# ChargeControl2019.net
KiCad netlist of a schematic drawn in Altium Designer
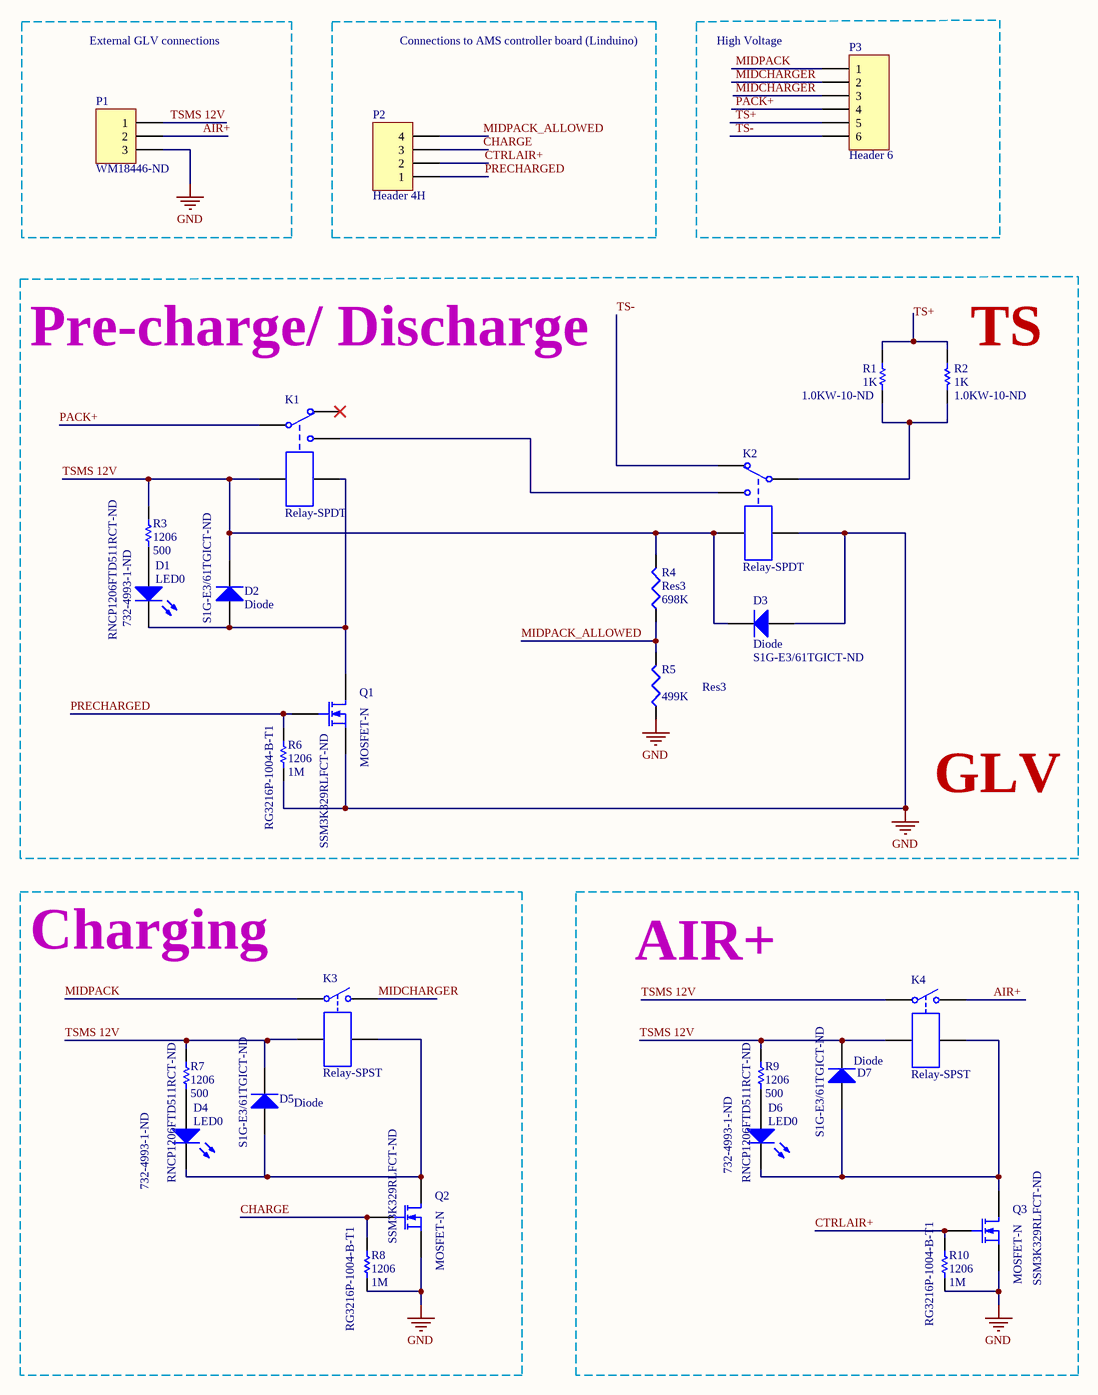
[diagram p0: ChargeControl2019.SchDoc]

(export (version "E")
  (design (tool "Eeschema 10.0.6"))
  (components
    (comp (ref "D1")
      (value "LED0")
      (footprint "LEDC3216X120NGRN")
      (description "Typical INFRARED GaAs LED")
      (fields
        (field (name "SUPPLIER PART NUMBER") "732-4993-1-ND")
        (field (name "PUBLISHER") "Altium Limited")
      )
      (libsource (lib "Miscellaneous Devices") (part "LED0"))
    )
    (comp (ref "D2")
      (value "Diode")
      (footprint "VISH-DO-214AC-SMA-2_N")
      (description "Switching diode")
      (fields
        (field (name "SUPPLIER PART NUMBER") "S1G-E3/61TGICT-ND")
        (field (name "PUBLISHER") "Altium Limited")
      )
      (libsource (lib "Miscellaneous Devices") (part "Diode"))
    )
    (comp (ref "D3")
      (value "Diode")
      (footprint "VISH-DO-214AC-SMA-2_N")
      (description "Switching diode")
      (fields
        (field (name "SUPPLIER PART NUMBER") "S1G-E3/61TGICT-ND")
        (field (name "PUBLISHER") "Altium Limited")
      )
      (libsource (lib "Miscellaneous Devices") (part "Diode"))
    )
    (comp (ref "D4")
      (value "LED0")
      (footprint "LEDC3216X120NGRN")
      (description "Typical INFRARED GaAs LED")
      (fields
        (field (name "SUPPLIER PART NUMBER") "732-4993-1-ND")
        (field (name "PUBLISHER") "Altium Limited")
      )
      (libsource (lib "Miscellaneous Devices") (part "LED0"))
    )
    (comp (ref "D5")
      (value "Diode")
      (footprint "VISH-DO-214AC-SMA-2_N")
      (description "Switching diode")
      (fields
        (field (name "SUPPLIER PART NUMBER") "S1G-E3/61TGICT-ND")
        (field (name "PUBLISHER") "Altium Limited")
      )
      (libsource (lib "Miscellaneous Devices") (part "Diode"))
    )
    (comp (ref "D6")
      (value "LED0")
      (footprint "LEDC3216X120NGRN")
      (description "Typical INFRARED GaAs LED")
      (fields
        (field (name "SUPPLIER PART NUMBER") "732-4993-1-ND")
        (field (name "PUBLISHER") "Altium Limited")
      )
      (libsource (lib "Miscellaneous Devices") (part "LED0"))
    )
    (comp (ref "D7")
      (value "Diode")
      (footprint "VISH-DO-214AC-SMA-2_N")
      (description "Switching diode")
      (fields
        (field (name "SUPPLIER PART NUMBER") "S1G-E3/61TGICT-ND")
        (field (name "PUBLISHER") "Altium Limited")
      )
      (libsource (lib "Miscellaneous Devices") (part "Diode"))
    )
    (comp (ref "K1")
      (value "Relay-SPDT")
      (footprint "G2RL1:G2RL14")
      (description "Single-Pole Dual-Throw Relay")
      (fields (field (name "PUBLISHER") "Altium Limited"))
      (libsource (lib "Miscellaneous Devices") (part "Relay-SPDT"))
    )
    (comp (ref "K2")
      (value "Relay-SPDT")
      (footprint "G2RL14")
      (description "Single-Pole Dual-Throw Relay")
      (fields (field (name "PUBLISHER") "Altium Limited"))
      (libsource (lib "Miscellaneous Devices") (part "Relay-SPDT"))
    )
    (comp (ref "K3")
      (value "Relay-SPST")
      (footprint "G2RL1ADC12")
      (description "Single-Pole Single-Throw Relay")
      (fields (field (name "PUBLISHER") "Altium Limited"))
      (libsource (lib "Miscellaneous Devices") (part "Relay-SPST"))
    )
    (comp (ref "K4")
      (value "Relay-SPST")
      (footprint "G2RL1ADC12")
      (description "Single-Pole Single-Throw Relay")
      (fields (field (name "PUBLISHER") "Altium Limited"))
      (libsource (lib "Miscellaneous Devices") (part "Relay-SPST"))
    )
    (comp (ref "P1")
      (value "Header 3")
      (footprint "Conn3pin")
      (description "3 pos wire to board")
      (fields (field (name "SUPPLIER PART NUMBER") "WM18446-ND") (field (name "PUBLISHER") "Altium Limited"))
      (libsource (lib "Miscellaneous Connectors") (part "Header 3"))
    )
    (comp (ref "P2")
      (value "Header 4H")
      (footprint "Conn4pin")
      (description "Header, 4-Pin, Right Angle")
      (fields (field (name "PUBLISHER") "Altium Limited"))
      (libsource (lib "Miscellaneous Connectors") (part "Header 4H"))
    )
    (comp (ref "P3")
      (value "Header 6")
      (footprint "Conn6pin")
      (description "Header, 6-Pin")
      (fields (field (name "PUBLISHER") "Altium Limited"))
      (libsource (lib "Miscellaneous Connectors") (part "Header 6"))
    )
    (comp (ref "Q1")
      (value "MOSFET-N")
      (footprint "SOT23-3")
      (description "N-Channel MOSFET")
      (fields
        (field (name "SUPPLIER PART NUMBER") "SSM3K329RLFCT-ND")
        (field (name "PUBLISHER") "Altium Limited")
      )
      (libsource (lib "Miscellaneous Devices") (part "MOSFET-N"))
    )
    (comp (ref "Q2")
      (value "MOSFET-N")
      (footprint "SOT23-3")
      (description "N-Channel MOSFET")
      (fields
        (field (name "SUPPLIER PART NUMBER") "SSM3K329RLFCT-ND")
        (field (name "PUBLISHER") "Altium Limited")
      )
      (libsource (lib "Miscellaneous Devices") (part "MOSFET-N"))
    )
    (comp (ref "Q3")
      (value "MOSFET-N")
      (footprint "SOT23-3")
      (description "N-Channel MOSFET")
      (fields
        (field (name "SUPPLIER PART NUMBER") "SSM3K329RLFCT-ND")
        (field (name "PUBLISHER") "Altium Limited")
      )
      (libsource (lib "Miscellaneous Devices") (part "MOSFET-N"))
    )
    (comp (ref "R1")
      (value "1K")
      (footprint "YAG_SQP10")
      (description "Resistor")
      (fields
        (field (name "SUPPLIER PART NUMBER") "1.0KW-10-ND")
        (field (name "Comment") "Res1")
        (field (name "PUBLISHER") "Altium Limited")
      )
      (libsource (lib "Miscellaneous Devices") (part "Res1"))
    )
    (comp (ref "R2")
      (value "1K")
      (footprint "YAG_SQP10")
      (description "Resistor")
      (fields
        (field (name "SUPPLIER PART NUMBER") "1.0KW-10-ND")
        (field (name "Comment") "Res1")
        (field (name "PUBLISHER") "Altium Limited")
      )
      (libsource (lib "Miscellaneous Devices") (part "Res1"))
    )
    (comp (ref "R3")
      (value "1206")
      (footprint "RESC3216X60N")
      (description "Resistor")
      (fields
        (field (name "ALTIUM_VALUE") "500")
        (field (name "SUPPLIER PART NUMBER") "RNCP1206FTD511RCT-ND")
        (field (name "PUBLISHER") "Altium Limited")
      )
      (libsource (lib "Miscellaneous Devices") (part "Res1"))
    )
    (comp (ref "R4")
      (value "Res3")
      (footprint "RESC3216X60N")
      (description "Resistor")
      (fields (field (name "ALTIUM_VALUE") "698K") (field (name "PUBLISHER") "Altium Limited"))
      (libsource (lib "Miscellaneous Devices") (part "Res3"))
    )
    (comp (ref "R5")
      (value "Res3")
      (footprint "RESC3216X60N")
      (description "Resistor")
      (fields (field (name "ALTIUM_VALUE") "499K") (field (name "PUBLISHER") "Altium Limited"))
      (libsource (lib "Miscellaneous Devices") (part "Res3"))
    )
    (comp (ref "R6")
      (value "1206")
      (footprint "RESC3216X60N")
      (description "Resistor")
      (fields
        (field (name "ALTIUM_VALUE") "1M")
        (field (name "SUPPLIER PART NUMBER") "RG3216P-1004-B-T1")
        (field (name "PUBLISHER") "Altium Limited")
      )
      (libsource (lib "Miscellaneous Devices") (part "Res1"))
    )
    (comp (ref "R7")
      (value "1206")
      (footprint "RESC3216X60N")
      (description "Resistor")
      (fields
        (field (name "ALTIUM_VALUE") "500")
        (field (name "SUPPLIER PART NUMBER") "RNCP1206FTD511RCT-ND")
        (field (name "PUBLISHER") "Altium Limited")
      )
      (libsource (lib "Miscellaneous Devices") (part "Res1"))
    )
    (comp (ref "R8")
      (value "1206")
      (footprint "RESC3216X60N")
      (description "Resistor")
      (fields
        (field (name "ALTIUM_VALUE") "1M")
        (field (name "SUPPLIER PART NUMBER") "RG3216P-1004-B-T1")
        (field (name "PUBLISHER") "Altium Limited")
      )
      (libsource (lib "Miscellaneous Devices") (part "Res1"))
    )
    (comp (ref "R9")
      (value "1206")
      (footprint "RESC3216X60N")
      (description "Resistor")
      (fields
        (field (name "ALTIUM_VALUE") "500")
        (field (name "SUPPLIER PART NUMBER") "RNCP1206FTD511RCT-ND")
        (field (name "PUBLISHER") "Altium Limited")
      )
      (libsource (lib "Miscellaneous Devices") (part "Res1"))
    )
    (comp (ref "R10")
      (value "1206")
      (footprint "RESC3216X60N")
      (description "Resistor")
      (fields
        (field (name "ALTIUM_VALUE") "1M")
        (field (name "SUPPLIER PART NUMBER") "RG3216P-1004-B-T1")
        (field (name "PUBLISHER") "Altium Limited")
      )
      (libsource (lib "Miscellaneous Devices") (part "Res1"))
    )
  )
  (nets
    (net (code "1") (name "/AIR+") (class "Default")
      (node (ref "K4") (pin "3") (pinfunction "3_3") (pintype "passive"))
      (node (ref "P1") (pin "2") (pinfunction "2_2") (pintype "passive"))
    )
    (net (code "2") (name "/CHARGE") (class "Default")
      (node (ref "P2") (pin "3") (pinfunction "3_3") (pintype "passive"))
      (node (ref "Q2") (pin "2") (pinfunction "G_2") (pintype "passive"))
      (node (ref "R8") (pin "2") (pinfunction "2_2") (pintype "passive"))
    )
    (net (code "3") (name "/CTRLAIR+") (class "Default")
      (node (ref "P2") (pin "2") (pinfunction "2_2") (pintype "passive"))
      (node (ref "Q3") (pin "2") (pinfunction "G_2") (pintype "passive"))
      (node (ref "R10") (pin "2") (pinfunction "2_2") (pintype "passive"))
    )
    (net (code "4") (name "/MIDCHARGER") (class "Default")
      (node (ref "K3") (pin "3") (pinfunction "3_3") (pintype "passive"))
      (node (ref "P3") (pin "2") (pinfunction "2_2") (pintype "passive"))
      (node (ref "P3") (pin "3") (pinfunction "3_3") (pintype "passive"))
    )
    (net (code "5") (name "/MIDPACK") (class "Default")
      (node (ref "K3") (pin "4") (pinfunction "4_4") (pintype "passive"))
      (node (ref "P3") (pin "1") (pinfunction "1_1") (pintype "passive"))
    )
    (net (code "6") (name "/MIDPACK_ALLOWED") (class "Default")
      (node (ref "P2") (pin "4") (pinfunction "4_4") (pintype "passive"))
      (node (ref "R4") (pin "1") (pinfunction "1_1") (pintype "passive"))
      (node (ref "R5") (pin "2") (pinfunction "2_2") (pintype "passive"))
    )
    (net (code "7") (name "/PACK+") (class "Default")
      (node (ref "K1") (pin "4") (pinfunction "4_4") (pintype "passive"))
      (node (ref "P3") (pin "4") (pinfunction "4_4") (pintype "passive"))
    )
    (net (code "8") (name "/PRECHARGED") (class "Default")
      (node (ref "P2") (pin "1") (pinfunction "1_1") (pintype "passive"))
      (node (ref "Q1") (pin "2") (pinfunction "G_2") (pintype "passive"))
      (node (ref "R6") (pin "2") (pinfunction "2_2") (pintype "passive"))
    )
    (net (code "9") (name "/TS+") (class "Default")
      (node (ref "P3") (pin "5") (pinfunction "5_5") (pintype "passive"))
      (node (ref "R1") (pin "2") (pinfunction "2_2") (pintype "passive"))
      (node (ref "R2") (pin "2") (pinfunction "2_2") (pintype "passive"))
    )
    (net (code "10") (name "/TS-") (class "Default")
      (node (ref "K2") (pin "2") (pinfunction "2_2") (pintype "passive"))
      (node (ref "P3") (pin "6") (pinfunction "6_6") (pintype "passive"))
    )
    (net (code "11") (name "/TSMS 12V") (class "Default")
      (node (ref "D2") (pin "2") (pinfunction "K_2") (pintype "passive"))
      (node (ref "D3") (pin "2") (pinfunction "K_2") (pintype "passive"))
      (node (ref "D5") (pin "2") (pinfunction "K_2") (pintype "passive"))
      (node (ref "D7") (pin "2") (pinfunction "K_2") (pintype "passive"))
      (node (ref "K1") (pin "1") (pinfunction "1_1") (pintype "passive"))
      (node (ref "K2") (pin "5") (pinfunction "5_5") (pintype "passive"))
      (node (ref "K3") (pin "1") (pinfunction "1_1") (pintype "passive"))
      (node (ref "K4") (pin "1") (pinfunction "1_1") (pintype "passive"))
      (node (ref "K4") (pin "4") (pinfunction "4_4") (pintype "passive"))
      (node (ref "P1") (pin "1") (pinfunction "1_1") (pintype "passive"))
      (node (ref "R3") (pin "1") (pinfunction "1_1") (pintype "passive"))
      (node (ref "R4") (pin "2") (pinfunction "2_2") (pintype "passive"))
      (node (ref "R7") (pin "1") (pinfunction "1_1") (pintype "passive"))
      (node (ref "R9") (pin "1") (pinfunction "1_1") (pintype "passive"))
    )
    (net (code "12") (name "GND") (class "Default")
      (node (ref "D3") (pin "1") (pinfunction "A_1") (pintype "passive"))
      (node (ref "K2") (pin "1") (pinfunction "1_1") (pintype "passive"))
      (node (ref "P1") (pin "3") (pinfunction "3_3") (pintype "passive"))
      (node (ref "Q1") (pin "3") (pinfunction "S_3") (pintype "passive"))
      (node (ref "Q2") (pin "3") (pinfunction "S_3") (pintype "passive"))
      (node (ref "Q3") (pin "3") (pinfunction "S_3") (pintype "passive"))
      (node (ref "R10") (pin "1") (pinfunction "1_1") (pintype "passive"))
      (node (ref "R5") (pin "1") (pinfunction "1_1") (pintype "passive"))
      (node (ref "R6") (pin "1") (pinfunction "1_1") (pintype "passive"))
      (node (ref "R8") (pin "1") (pinfunction "1_1") (pintype "passive"))
    )
    (net (code "13") (name "Net-(D1-A)") (class "Default")
      (node (ref "D1") (pin "1") (pinfunction "A_1") (pintype "passive"))
      (node (ref "R3") (pin "2") (pinfunction "2_2") (pintype "passive"))
    )
    (net (code "14") (name "Net-(D1-K)") (class "Default")
      (node (ref "D1") (pin "2") (pinfunction "K_2") (pintype "passive"))
      (node (ref "D2") (pin "1") (pinfunction "A_1") (pintype "passive"))
      (node (ref "K1") (pin "5") (pinfunction "5_5") (pintype "passive"))
      (node (ref "Q1") (pin "1") (pinfunction "D_1") (pintype "passive"))
    )
    (net (code "15") (name "Net-(D4-A)") (class "Default")
      (node (ref "D4") (pin "1") (pinfunction "A_1") (pintype "passive"))
      (node (ref "R7") (pin "2") (pinfunction "2_2") (pintype "passive"))
    )
    (net (code "16") (name "Net-(D4-K)") (class "Default")
      (node (ref "D4") (pin "2") (pinfunction "K_2") (pintype "passive"))
      (node (ref "D5") (pin "1") (pinfunction "A_1") (pintype "passive"))
      (node (ref "K3") (pin "5") (pinfunction "5_5") (pintype "passive"))
      (node (ref "Q2") (pin "1") (pinfunction "D_1") (pintype "passive"))
    )
    (net (code "17") (name "Net-(D6-A)") (class "Default")
      (node (ref "D6") (pin "1") (pinfunction "A_1") (pintype "passive"))
      (node (ref "R9") (pin "2") (pinfunction "2_2") (pintype "passive"))
    )
    (net (code "18") (name "Net-(D6-K)") (class "Default")
      (node (ref "D6") (pin "2") (pinfunction "K_2") (pintype "passive"))
      (node (ref "D7") (pin "1") (pinfunction "A_1") (pintype "passive"))
      (node (ref "K4") (pin "5") (pinfunction "5_5") (pintype "passive"))
      (node (ref "Q3") (pin "1") (pinfunction "D_1") (pintype "passive"))
    )
    (net (code "19") (name "Net-(K1-Pad3)") (class "Default")
      (node (ref "K1") (pin "3") (pinfunction "3_3") (pintype "passive"))
      (node (ref "K2") (pin "3") (pinfunction "3_3") (pintype "passive"))
    )
    (net (code "20") (name "Net-(K2-Pad4)") (class "Default")
      (node (ref "K2") (pin "4") (pinfunction "4_4") (pintype "passive"))
      (node (ref "R1") (pin "1") (pinfunction "1_1") (pintype "passive"))
      (node (ref "R2") (pin "1") (pinfunction "1_1") (pintype "passive"))
    )
    (net (code "21") (name "unconnected-(K1-Pad2)") (class "Default")
      (node (ref "K1") (pin "2") (pinfunction "2_2") (pintype "passive+no_connect"))
    )
  )
)
